# PWM_Presence_Detection.net
KiCad netlist of a schematic drawn in EasyEDA
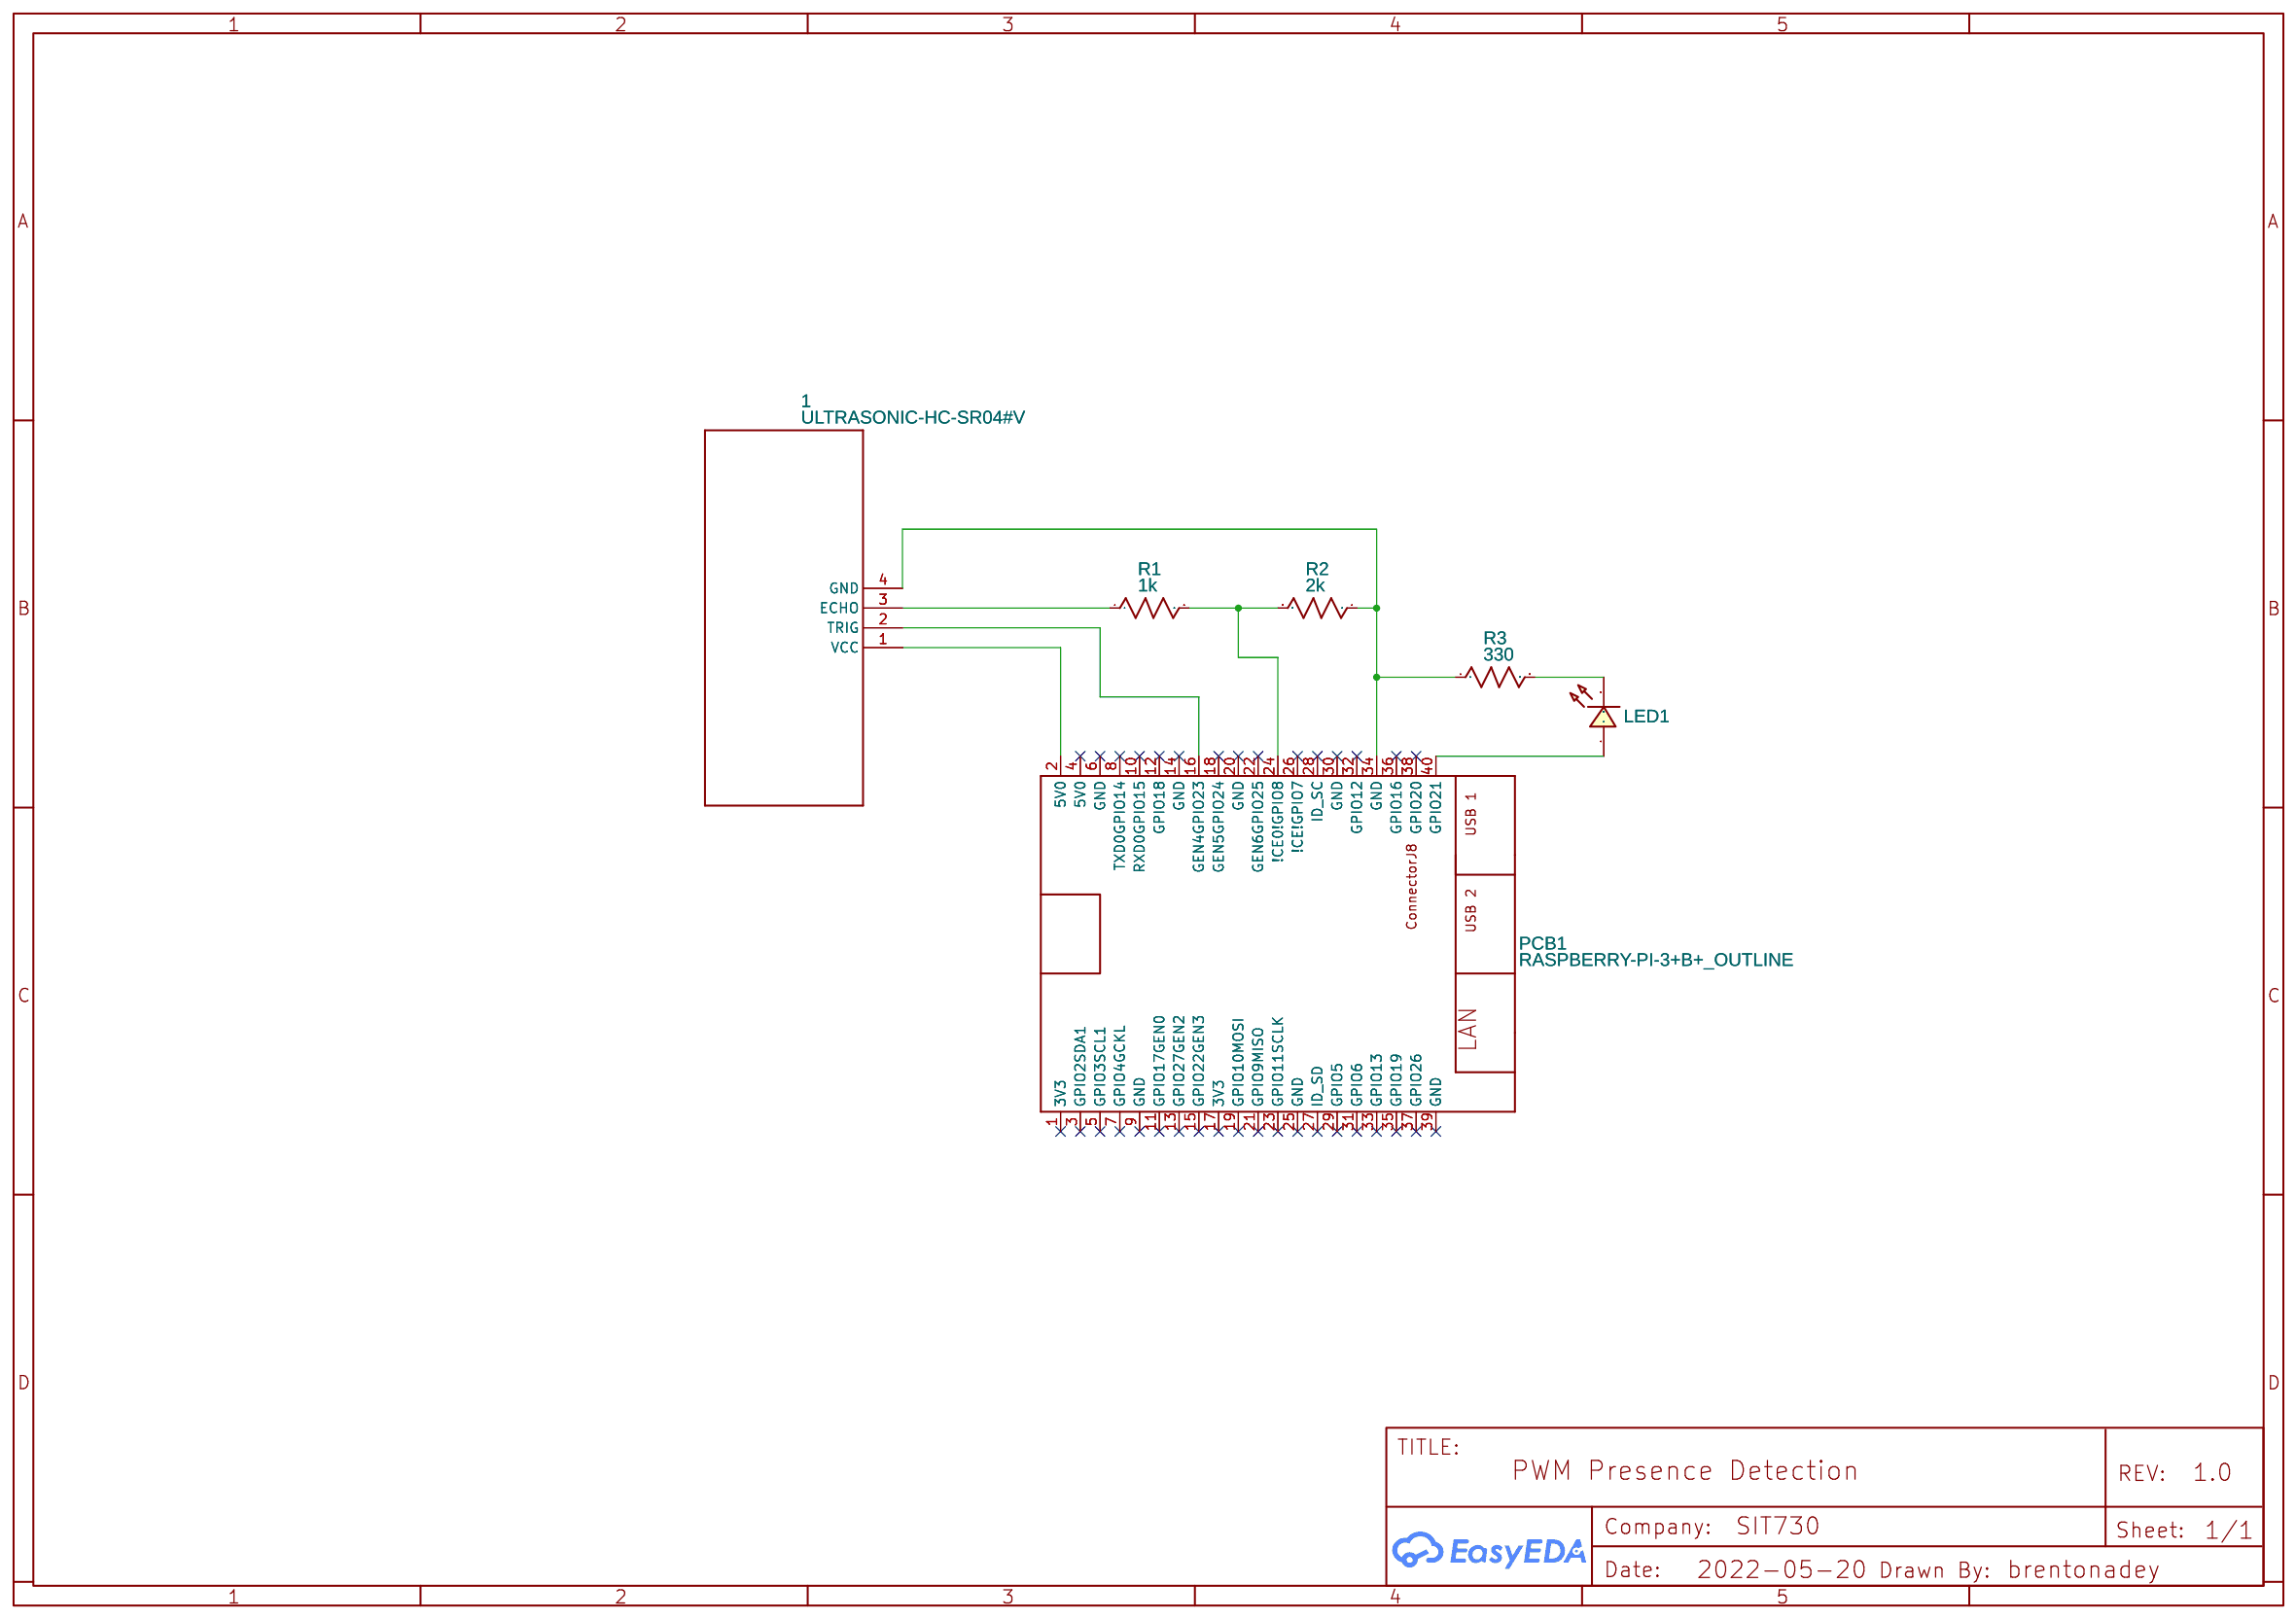
[diagram p0: schematic sheet]

(export (version "E")
  (design (tool "Eeschema 10.0.6"))
  (components
    (comp (ref "1") (value "ULTRASONIC-HC-SR04#V") (libsource (lib "") (part "ULTRASONIC-HC-SR04#V")))
    (comp (ref "LED1")
      (value "LED-0603_B")
      (fields
        (field (name "BOM_Manufacturer Part") "19-217/BHC-ZL1M2RY/3T")
        (field (name "BOM_Supplier Part") "C72041")
      )
      (libsource (lib "") (part "LED-0603_B"))
    )
    (comp (ref "PCB1")
      (value "RASPBERRY-PI-3+B+_OUTLINE")
      (libsource (lib "") (part "RASPBERRY-PI-3+B+_OUTLINE"))
    )
    (comp (ref "R1") (value "1k") (libsource (lib "") (part "R_0603_US")))
    (comp (ref "R2") (value "2k") (libsource (lib "") (part "R_0603_US_1")))
    (comp (ref "R3") (value "330") (libsource (lib "") (part "R_0603_US")))
  )
  (nets
    (net (code "1") (name "Net-(1-ECHO)") (class "Default")
      (node (ref "1") (pin "3") (pinfunction "ECHO_3") (pintype "bidirectional"))
      (node (ref "R1") (pin "1") (pinfunction "1_1") (pintype "unspecified"))
    )
    (net (code "2") (name "Net-(1-GND)") (class "Default")
      (node (ref "1") (pin "4") (pinfunction "GND_4") (pintype "bidirectional"))
      (node (ref "PCB1") (pin "34") (pinfunction "GND_34") (pintype "unspecified"))
      (node (ref "R2") (pin "1") (pinfunction "1_1") (pintype "unspecified"))
      (node (ref "R3") (pin "1") (pinfunction "1_1") (pintype "unspecified"))
    )
    (net (code "3") (name "Net-(1-TRIG)") (class "Default")
      (node (ref "1") (pin "2") (pinfunction "TRIG_2") (pintype "bidirectional"))
      (node (ref "PCB1") (pin "16") (pinfunction "GEN4GPIO23_16") (pintype "unspecified"))
    )
    (net (code "4") (name "Net-(1-VCC)") (class "Default")
      (node (ref "1") (pin "1") (pinfunction "VCC_1") (pintype "bidirectional"))
      (node (ref "PCB1") (pin "2") (pinfunction "5V0_2") (pintype "unspecified"))
    )
    (net (code "5") (name "Net-(LED1-Pad2)") (class "Default")
      (node (ref "LED1") (pin "2") (pinfunction "2_2") (pintype "unspecified"))
      (node (ref "R3") (pin "2") (pinfunction "2_2") (pintype "unspecified"))
    )
    (net (code "6") (name "Net-(PCB1-!CE0!GPIO8)") (class "Default")
      (node (ref "PCB1") (pin "24") (pinfunction "!CE0!GPIO8_24") (pintype "unspecified"))
      (node (ref "R1") (pin "2") (pinfunction "2_2") (pintype "unspecified"))
      (node (ref "R2") (pin "2") (pinfunction "2_2") (pintype "unspecified"))
    )
    (net (code "7") (name "Net-(PCB1-GPIO21)") (class "Default")
      (node (ref "LED1") (pin "1") (pinfunction "1_1") (pintype "unspecified"))
      (node (ref "PCB1") (pin "40") (pinfunction "GPIO21_40") (pintype "unspecified"))
    )
    (net (code "8") (name "unconnected-(PCB1-!CE!GPIO7-Pad26)") (class "Default")
      (node (ref "PCB1") (pin "26") (pinfunction "!CE!GPIO7_26") (pintype "unspecified+no_connect"))
    )
    (net (code "9") (name "unconnected-(PCB1-3V3-Pad1)") (class "Default")
      (node (ref "PCB1") (pin "1") (pinfunction "3V3_1") (pintype "unspecified+no_connect"))
    )
    (net (code "10") (name "unconnected-(PCB1-3V3-Pad17)") (class "Default")
      (node (ref "PCB1") (pin "17") (pinfunction "3V3_17") (pintype "unspecified+no_connect"))
    )
    (net (code "11") (name "unconnected-(PCB1-5V0-Pad4)") (class "Default")
      (node (ref "PCB1") (pin "4") (pinfunction "5V0_4") (pintype "unspecified+no_connect"))
    )
    (net (code "12") (name "unconnected-(PCB1-GEN5GPIO24-Pad18)") (class "Default")
      (node (ref "PCB1") (pin "18") (pinfunction "GEN5GPIO24_18") (pintype "unspecified+no_connect"))
    )
    (net (code "13") (name "unconnected-(PCB1-GEN6GPIO25-Pad22)") (class "Default")
      (node (ref "PCB1") (pin "22") (pinfunction "GEN6GPIO25_22") (pintype "unspecified+no_connect"))
    )
    (net (code "14") (name "unconnected-(PCB1-GND-Pad6)") (class "Default")
      (node (ref "PCB1") (pin "6") (pinfunction "GND_6") (pintype "unspecified+no_connect"))
    )
    (net (code "15") (name "unconnected-(PCB1-GND-Pad9)") (class "Default")
      (node (ref "PCB1") (pin "9") (pinfunction "GND_9") (pintype "unspecified+no_connect"))
    )
    (net (code "16") (name "unconnected-(PCB1-GND-Pad14)") (class "Default")
      (node (ref "PCB1") (pin "14") (pinfunction "GND_14") (pintype "unspecified+no_connect"))
    )
    (net (code "17") (name "unconnected-(PCB1-GND-Pad20)") (class "Default")
      (node (ref "PCB1") (pin "20") (pinfunction "GND_20") (pintype "unspecified+no_connect"))
    )
    (net (code "18") (name "unconnected-(PCB1-GND-Pad25)") (class "Default")
      (node (ref "PCB1") (pin "25") (pinfunction "GND_25") (pintype "unspecified+no_connect"))
    )
    (net (code "19") (name "unconnected-(PCB1-GND-Pad30)") (class "Default")
      (node (ref "PCB1") (pin "30") (pinfunction "GND_30") (pintype "unspecified+no_connect"))
    )
    (net (code "20") (name "unconnected-(PCB1-GND-Pad39)") (class "Default")
      (node (ref "PCB1") (pin "39") (pinfunction "GND_39") (pintype "unspecified+no_connect"))
    )
    (net (code "21") (name "unconnected-(PCB1-GPIO2SDA1-Pad3)") (class "Default")
      (node (ref "PCB1") (pin "3") (pinfunction "GPIO2SDA1_3") (pintype "unspecified+no_connect"))
    )
    (net (code "22") (name "unconnected-(PCB1-GPIO3SCL1-Pad5)") (class "Default")
      (node (ref "PCB1") (pin "5") (pinfunction "GPIO3SCL1_5") (pintype "unspecified+no_connect"))
    )
    (net (code "23") (name "unconnected-(PCB1-GPIO4GCKL-Pad7)") (class "Default")
      (node (ref "PCB1") (pin "7") (pinfunction "GPIO4GCKL_7") (pintype "unspecified+no_connect"))
    )
    (net (code "24") (name "unconnected-(PCB1-GPIO5-Pad29)") (class "Default")
      (node (ref "PCB1") (pin "29") (pinfunction "GPIO5_29") (pintype "unspecified+no_connect"))
    )
    (net (code "25") (name "unconnected-(PCB1-GPIO6-Pad31)") (class "Default")
      (node (ref "PCB1") (pin "31") (pinfunction "GPIO6_31") (pintype "unspecified+no_connect"))
    )
    (net (code "26") (name "unconnected-(PCB1-GPIO9MISO-Pad21)") (class "Default")
      (node (ref "PCB1") (pin "21") (pinfunction "GPIO9MISO_21") (pintype "unspecified+no_connect"))
    )
    (net (code "27") (name "unconnected-(PCB1-GPIO10MOSI-Pad19)") (class "Default")
      (node (ref "PCB1") (pin "19") (pinfunction "GPIO10MOSI_19") (pintype "unspecified+no_connect"))
    )
    (net (code "28") (name "unconnected-(PCB1-GPIO11SCLK-Pad23)") (class "Default")
      (node (ref "PCB1") (pin "23") (pinfunction "GPIO11SCLK_23") (pintype "unspecified+no_connect"))
    )
    (net (code "29") (name "unconnected-(PCB1-GPIO12-Pad32)") (class "Default")
      (node (ref "PCB1") (pin "32") (pinfunction "GPIO12_32") (pintype "unspecified+no_connect"))
    )
    (net (code "30") (name "unconnected-(PCB1-GPIO13-Pad33)") (class "Default")
      (node (ref "PCB1") (pin "33") (pinfunction "GPIO13_33") (pintype "unspecified+no_connect"))
    )
    (net (code "31") (name "unconnected-(PCB1-GPIO16-Pad36)") (class "Default")
      (node (ref "PCB1") (pin "36") (pinfunction "GPIO16_36") (pintype "unspecified+no_connect"))
    )
    (net (code "32") (name "unconnected-(PCB1-GPIO17GEN0-Pad11)") (class "Default")
      (node (ref "PCB1") (pin "11") (pinfunction "GPIO17GEN0_11") (pintype "unspecified+no_connect"))
    )
    (net (code "33") (name "unconnected-(PCB1-GPIO18-Pad12)") (class "Default")
      (node (ref "PCB1") (pin "12") (pinfunction "GPIO18_12") (pintype "unspecified+no_connect"))
    )
    (net (code "34") (name "unconnected-(PCB1-GPIO19-Pad35)") (class "Default")
      (node (ref "PCB1") (pin "35") (pinfunction "GPIO19_35") (pintype "unspecified+no_connect"))
    )
    (net (code "35") (name "unconnected-(PCB1-GPIO20-Pad38)") (class "Default")
      (node (ref "PCB1") (pin "38") (pinfunction "GPIO20_38") (pintype "unspecified+no_connect"))
    )
    (net (code "36") (name "unconnected-(PCB1-GPIO22GEN3-Pad15)") (class "Default")
      (node (ref "PCB1") (pin "15") (pinfunction "GPIO22GEN3_15") (pintype "unspecified+no_connect"))
    )
    (net (code "37") (name "unconnected-(PCB1-GPIO26-Pad37)") (class "Default")
      (node (ref "PCB1") (pin "37") (pinfunction "GPIO26_37") (pintype "unspecified+no_connect"))
    )
    (net (code "38") (name "unconnected-(PCB1-GPIO27GEN2-Pad13)") (class "Default")
      (node (ref "PCB1") (pin "13") (pinfunction "GPIO27GEN2_13") (pintype "unspecified+no_connect"))
    )
    (net (code "39") (name "unconnected-(PCB1-ID_SC-Pad28)") (class "Default")
      (node (ref "PCB1") (pin "28") (pinfunction "ID_SC_28") (pintype "unspecified+no_connect"))
    )
    (net (code "40") (name "unconnected-(PCB1-ID_SD-Pad27)") (class "Default")
      (node (ref "PCB1") (pin "27") (pinfunction "ID_SD_27") (pintype "unspecified+no_connect"))
    )
    (net (code "41") (name "unconnected-(PCB1-RXD0GPIO15-Pad10)") (class "Default")
      (node (ref "PCB1") (pin "10") (pinfunction "RXD0GPIO15_10") (pintype "unspecified+no_connect"))
    )
    (net (code "42") (name "unconnected-(PCB1-TXD0GPIO14-Pad8)") (class "Default")
      (node (ref "PCB1") (pin "8") (pinfunction "TXD0GPIO14_8") (pintype "unspecified+no_connect"))
    )
  )
)
